# MCU.net
KiCad netlist of a schematic drawn in Altium Designer
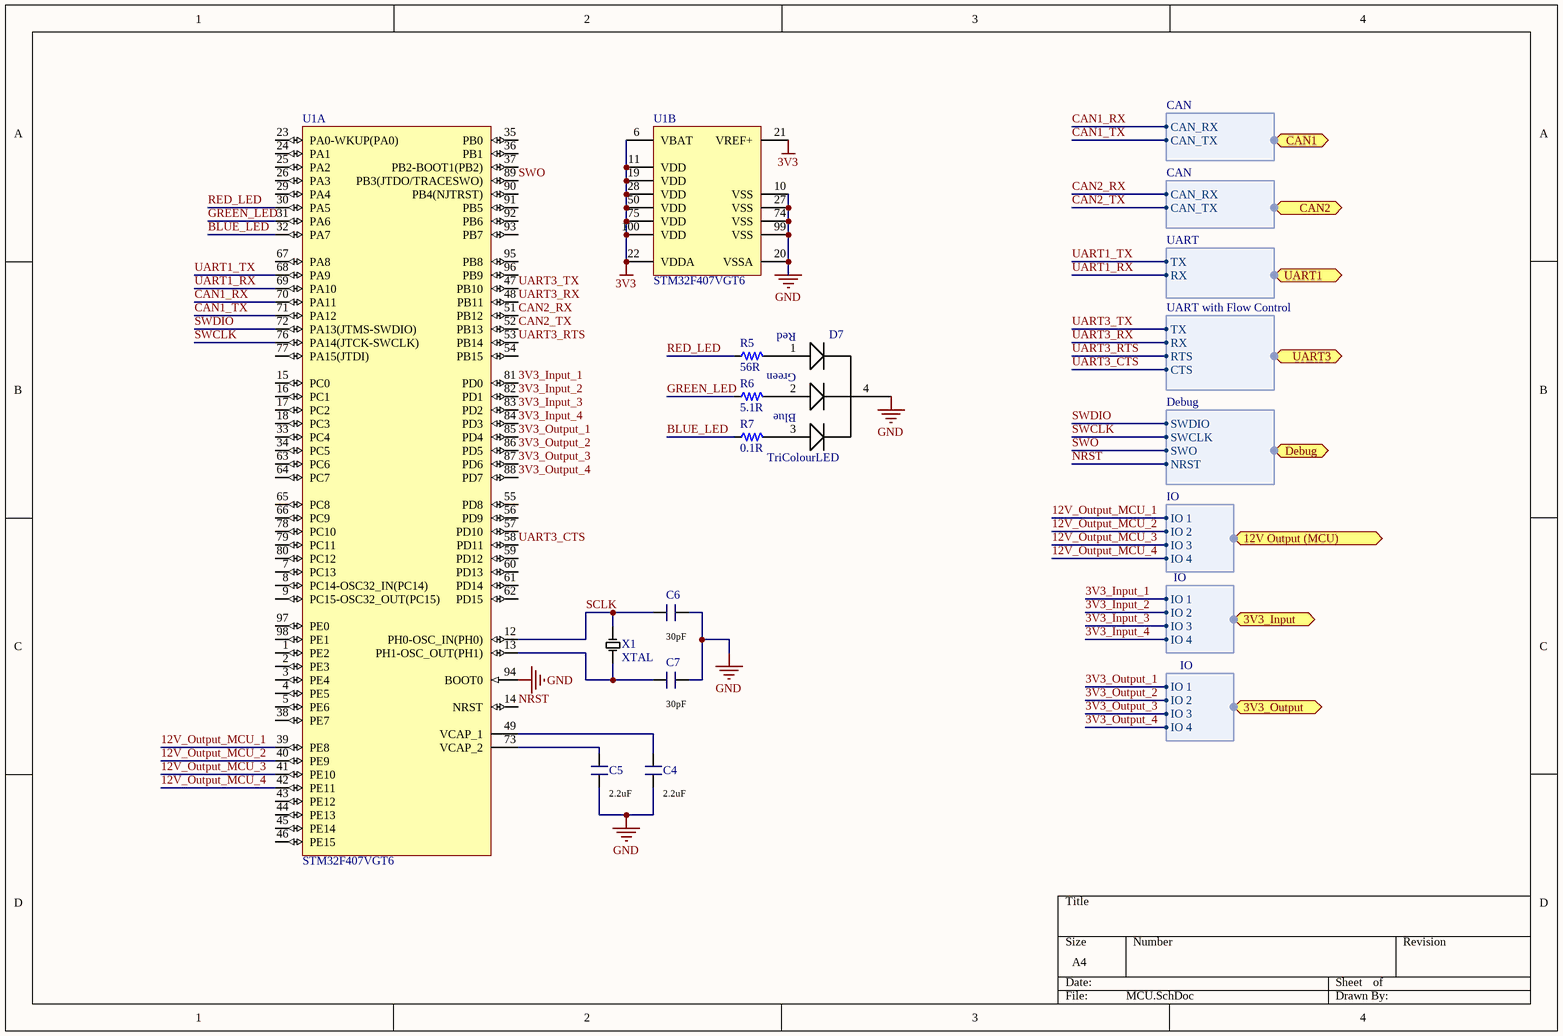
[diagram p0: MCU.SchDoc]

(export (version "E")
  (design (tool "Eeschema 10.0.6"))
  (components
    (comp (ref "C4")
      (value "SCH_GENERIC_CAPACITOR_0603")
      (footprint "PCB_GENERIC_SMD_0603")
      (description "Generic SMD capacitor 0603")
      (fields (field (name "TOLERANCE") "*%") (field (name "CAPACITANCE") "2.2uF"))
      (libsource (lib "Capacitors") (part "SCH_GENERIC_CAPACITOR_0603"))
    )
    (comp (ref "C5")
      (value "SCH_GENERIC_CAPACITOR_0603")
      (footprint "PCB_GENERIC_SMD_0603")
      (description "Generic SMD capacitor 0603")
      (fields (field (name "TOLERANCE") "*%") (field (name "CAPACITANCE") "2.2uF"))
      (libsource (lib "Capacitors") (part "SCH_GENERIC_CAPACITOR_0603"))
    )
    (comp (ref "C6")
      (value "SCH_GENERIC_CAPACITOR_0603")
      (footprint "PCB_GENERIC_SMD_0603")
      (description "Generic SMD capacitor 0603")
      (fields (field (name "TOLERANCE") "*%") (field (name "CAPACITANCE") "30pF"))
      (libsource (lib "Capacitors") (part "SCH_GENERIC_CAPACITOR_0603"))
    )
    (comp (ref "C7")
      (value "SCH_GENERIC_CAPACITOR_0603")
      (footprint "PCB_GENERIC_SMD_0603")
      (description "Generic SMD capacitor 0603")
      (fields (field (name "TOLERANCE") "*%") (field (name "CAPACITANCE") "30pF"))
      (libsource (lib "Capacitors") (part "SCH_GENERIC_CAPACITOR_0603"))
    )
    (comp (ref "D7")
      (value "TriColourLED")
      (footprint "TricolourLED - SunLED - DK  1497-1225-2-ND")
      (libsource (lib "TricolourLED - SunLED - DK 1497-1225-2-ND") (part "TriColourLED"))
    )
    (comp (ref "R5")
      (value "SCH_GENERIC_RESISTOR_0603")
      (footprint "PCB_GENERIC_SMD_0603")
      (description "Generic SMD resistor 0603")
      (fields (field (name "RESISTANCE") "56R"))
      (libsource (lib "SCH_GENERIC_RESISTOR_0603") (part "SCH_GENERIC_RESISTOR_0603"))
    )
    (comp (ref "R6")
      (value "SCH_GENERIC_RESISTOR_0603")
      (footprint "PCB_GENERIC_SMD_0603")
      (description "Generic SMD resistor 0603")
      (fields (field (name "RESISTANCE") "5.1R"))
      (libsource (lib "SCH_GENERIC_RESISTOR_0603") (part "SCH_GENERIC_RESISTOR_0603"))
    )
    (comp (ref "R7")
      (value "SCH_GENERIC_RESISTOR_0603")
      (footprint "PCB_GENERIC_SMD_0603")
      (description "Generic SMD resistor 0603")
      (fields (field (name "RESISTANCE") "0.1R"))
      (libsource (lib "SCH_GENERIC_RESISTOR_0603") (part "SCH_GENERIC_RESISTOR_0603"))
    )
    (comp (ref "U1")
      (value "STM32F407VGT6")
      (footprint "STM-LQFP100_M")
      (fields (field (name "MANUFACTURER") "STMicroelectronics"))
      (libsource (lib "STMicroelectronics STM32 F4") (part "STM32F407VGT6"))
    )
    (comp (ref "X1") (value "XTAL") (footprint "CRYSTAL_8MHZ") (libsource (lib "Crystal") (part "Crystal")))
  )
  (nets
    (net (code "8") (name "/3V3_Input_1") (class "Default")
      (node (ref "U1") (pin "81") (pinfunction "PD0_81") (pintype "bidirectional"))
    )
    (net (code "9") (name "/3V3_Input_2") (class "Default")
      (node (ref "U1") (pin "82") (pinfunction "PD1_82") (pintype "bidirectional"))
    )
    (net (code "10") (name "/3V3_Input_3") (class "Default")
      (node (ref "U1") (pin "83") (pinfunction "PD2_83") (pintype "bidirectional"))
    )
    (net (code "11") (name "/3V3_Input_4") (class "Default")
      (node (ref "U1") (pin "84") (pinfunction "PD3_84") (pintype "bidirectional"))
    )
    (net (code "12") (name "/3V3_Output_1") (class "Default")
      (node (ref "U1") (pin "85") (pinfunction "PD4_85") (pintype "bidirectional"))
    )
    (net (code "13") (name "/3V3_Output_2") (class "Default")
      (node (ref "U1") (pin "86") (pinfunction "PD5_86") (pintype "bidirectional"))
    )
    (net (code "14") (name "/3V3_Output_3") (class "Default")
      (node (ref "U1") (pin "87") (pinfunction "PD6_87") (pintype "bidirectional"))
    )
    (net (code "15") (name "/3V3_Output_4") (class "Default")
      (node (ref "U1") (pin "88") (pinfunction "PD7_88") (pintype "bidirectional"))
    )
    (net (code "16") (name "/12V_Output_MCU_1") (class "Default")
      (node (ref "U1") (pin "39") (pinfunction "PE8_39") (pintype "bidirectional"))
    )
    (net (code "17") (name "/12V_Output_MCU_2") (class "Default")
      (node (ref "U1") (pin "40") (pinfunction "PE9_40") (pintype "bidirectional"))
    )
    (net (code "18") (name "/12V_Output_MCU_3") (class "Default")
      (node (ref "U1") (pin "41") (pinfunction "PE10_41") (pintype "bidirectional"))
    )
    (net (code "19") (name "/12V_Output_MCU_4") (class "Default")
      (node (ref "U1") (pin "42") (pinfunction "PE11_42") (pintype "bidirectional"))
    )
    (net (code "20") (name "/BLUE_LED") (class "Default")
      (node (ref "R7") (pin "1") (pinfunction "1_1") (pintype "passive"))
      (node (ref "U1") (pin "32") (pinfunction "PA7_32") (pintype "bidirectional"))
    )
    (net (code "21") (name "/CAN1_RX") (class "Default")
      (node (ref "U1") (pin "70") (pinfunction "PA11_70") (pintype "bidirectional"))
    )
    (net (code "22") (name "/CAN1_TX") (class "Default")
      (node (ref "U1") (pin "71") (pinfunction "PA12_71") (pintype "bidirectional"))
    )
    (net (code "23") (name "/CAN2_RX") (class "Default")
      (node (ref "U1") (pin "51") (pinfunction "PB12_51") (pintype "bidirectional"))
    )
    (net (code "24") (name "/CAN2_TX") (class "Default")
      (node (ref "U1") (pin "52") (pinfunction "PB13_52") (pintype "bidirectional"))
    )
    (net (code "25") (name "/GREEN_LED") (class "Default")
      (node (ref "R6") (pin "1") (pinfunction "1_1") (pintype "passive"))
      (node (ref "U1") (pin "31") (pinfunction "PA6_31") (pintype "bidirectional"))
    )
    (net (code "26") (name "/NRST") (class "Default")
      (node (ref "U1") (pin "14") (pinfunction "NRST_14") (pintype "bidirectional"))
    )
    (net (code "27") (name "/RED_LED") (class "Default")
      (node (ref "R5") (pin "1") (pinfunction "1_1") (pintype "passive"))
      (node (ref "U1") (pin "30") (pinfunction "PA5_30") (pintype "bidirectional"))
    )
    (net (code "28") (name "/SCLK") (class "Default")
      (node (ref "C6") (pin "2") (pinfunction "2_2") (pintype "passive"))
      (node (ref "U1") (pin "12") (pinfunction "PH0-OSC_IN(PH0)_12") (pintype "bidirectional"))
      (node (ref "X1") (pin "1") (pintype "passive"))
    )
    (net (code "29") (name "/SWCLK") (class "Default")
      (node (ref "U1") (pin "76") (pinfunction "PA14(JTCK-SWCLK)_76") (pintype "bidirectional"))
    )
    (net (code "30") (name "/SWDIO") (class "Default")
      (node (ref "U1") (pin "72") (pinfunction "PA13(JTMS-SWDIO)_72") (pintype "bidirectional"))
    )
    (net (code "31") (name "/SWO") (class "Default")
      (node (ref "U1") (pin "89") (pinfunction "PB3(JTDO/TRACESWO)_89") (pintype "bidirectional"))
    )
    (net (code "32") (name "/UART1_RX") (class "Default")
      (node (ref "U1") (pin "69") (pinfunction "PA10_69") (pintype "bidirectional"))
    )
    (net (code "33") (name "/UART1_TX") (class "Default")
      (node (ref "U1") (pin "68") (pinfunction "PA9_68") (pintype "bidirectional"))
    )
    (net (code "34") (name "/UART3_CTS") (class "Default")
      (node (ref "U1") (pin "58") (pinfunction "PD11_58") (pintype "bidirectional"))
    )
    (net (code "35") (name "/UART3_RTS") (class "Default")
      (node (ref "U1") (pin "53") (pinfunction "PB14_53") (pintype "bidirectional"))
    )
    (net (code "36") (name "/UART3_RX") (class "Default")
      (node (ref "U1") (pin "48") (pinfunction "PB11_48") (pintype "bidirectional"))
    )
    (net (code "37") (name "/UART3_TX") (class "Default")
      (node (ref "U1") (pin "47") (pinfunction "PB10_47") (pintype "bidirectional"))
    )
    (net (code "43") (name "3V3") (class "Default")
      (node (ref "U1") (pin "100") (pinfunction "VDD_100") (pintype "power_in"))
      (node (ref "U1") (pin "11") (pinfunction "VDD_11") (pintype "power_in"))
      (node (ref "U1") (pin "19") (pinfunction "VDD_19") (pintype "power_in"))
      (node (ref "U1") (pin "21") (pinfunction "VREF+_21") (pintype "power_in"))
      (node (ref "U1") (pin "22") (pinfunction "VDDA_22") (pintype "power_in"))
      (node (ref "U1") (pin "28") (pinfunction "VDD_28") (pintype "power_in"))
      (node (ref "U1") (pin "50") (pinfunction "VDD_50") (pintype "power_in"))
      (node (ref "U1") (pin "6") (pinfunction "VBAT_6") (pintype "power_in"))
      (node (ref "U1") (pin "75") (pinfunction "VDD_75") (pintype "power_in"))
    )
    (net (code "44") (name "GND") (class "Default")
      (node (ref "C4") (pin "1") (pinfunction "1_1") (pintype "passive"))
      (node (ref "C5") (pin "1") (pinfunction "1_1") (pintype "passive"))
      (node (ref "C6") (pin "1") (pinfunction "1_1") (pintype "passive"))
      (node (ref "C7") (pin "1") (pinfunction "1_1") (pintype "passive"))
      (node (ref "D7") (pin "4") (pinfunction "4_4") (pintype "passive"))
      (node (ref "U1") (pin "10") (pinfunction "VSS_10") (pintype "power_in"))
      (node (ref "U1") (pin "20") (pinfunction "VSSA_20") (pintype "power_in"))
      (node (ref "U1") (pin "27") (pinfunction "VSS_27") (pintype "power_in"))
      (node (ref "U1") (pin "74") (pinfunction "VSS_74") (pintype "power_in"))
      (node (ref "U1") (pin "94") (pinfunction "BOOT0_94") (pintype "input"))
      (node (ref "U1") (pin "99") (pinfunction "VSS_99") (pintype "power_in"))
    )
    (net (code "45") (name "Net-(D7-Blue)") (class "Default")
      (node (ref "D7") (pin "3") (pinfunction "Blue_3") (pintype "passive"))
      (node (ref "R7") (pin "2") (pinfunction "2_2") (pintype "passive"))
    )
    (net (code "46") (name "Net-(D7-Green)") (class "Default")
      (node (ref "D7") (pin "2") (pinfunction "Green_2") (pintype "passive"))
      (node (ref "R6") (pin "2") (pinfunction "2_2") (pintype "passive"))
    )
    (net (code "47") (name "Net-(D7-Red)") (class "Default")
      (node (ref "D7") (pin "1") (pinfunction "Red_1") (pintype "passive"))
      (node (ref "R5") (pin "2") (pinfunction "2_2") (pintype "passive"))
    )
    (net (code "48") (name "Net-(U1A-PH1-OSC_OUT(PH1))") (class "Default")
      (node (ref "C7") (pin "2") (pinfunction "2_2") (pintype "passive"))
      (node (ref "U1") (pin "13") (pinfunction "PH1-OSC_OUT(PH1)_13") (pintype "bidirectional"))
      (node (ref "X1") (pin "2") (pintype "passive"))
    )
    (net (code "49") (name "Net-(U1A-VCAP_1)") (class "Default")
      (node (ref "C4") (pin "2") (pinfunction "2_2") (pintype "passive"))
      (node (ref "U1") (pin "49") (pinfunction "VCAP_1_49") (pintype "power_in"))
    )
    (net (code "50") (name "Net-(U1A-VCAP_2)") (class "Default")
      (node (ref "C5") (pin "2") (pinfunction "2_2") (pintype "passive"))
      (node (ref "U1") (pin "73") (pinfunction "VCAP_2_73") (pintype "power_in"))
    )
    (net (code "51") (name "unconnected-(U1A-PA0-WKUP(PA0)-Pad23)") (class "Default")
      (node (ref "U1") (pin "23") (pinfunction "PA0-WKUP(PA0)_23") (pintype "bidirectional"))
    )
    (net (code "52") (name "unconnected-(U1A-PA1-Pad24)") (class "Default")
      (node (ref "U1") (pin "24") (pinfunction "PA1_24") (pintype "bidirectional"))
    )
    (net (code "53") (name "unconnected-(U1A-PA2-Pad25)") (class "Default")
      (node (ref "U1") (pin "25") (pinfunction "PA2_25") (pintype "bidirectional"))
    )
    (net (code "54") (name "unconnected-(U1A-PA3-Pad26)") (class "Default")
      (node (ref "U1") (pin "26") (pinfunction "PA3_26") (pintype "bidirectional"))
    )
    (net (code "55") (name "unconnected-(U1A-PA4-Pad29)") (class "Default")
      (node (ref "U1") (pin "29") (pinfunction "PA4_29") (pintype "bidirectional"))
    )
    (net (code "56") (name "unconnected-(U1A-PA8-Pad67)") (class "Default")
      (node (ref "U1") (pin "67") (pinfunction "PA8_67") (pintype "bidirectional"))
    )
    (net (code "57") (name "unconnected-(U1A-PA15(JTDI)-Pad77)") (class "Default")
      (node (ref "U1") (pin "77") (pinfunction "PA15(JTDI)_77") (pintype "bidirectional"))
    )
    (net (code "58") (name "unconnected-(U1A-PB0-Pad35)") (class "Default")
      (node (ref "U1") (pin "35") (pinfunction "PB0_35") (pintype "bidirectional"))
    )
    (net (code "59") (name "unconnected-(U1A-PB1-Pad36)") (class "Default")
      (node (ref "U1") (pin "36") (pinfunction "PB1_36") (pintype "bidirectional"))
    )
    (net (code "60") (name "unconnected-(U1A-PB2-BOOT1(PB2)-Pad37)") (class "Default")
      (node (ref "U1") (pin "37") (pinfunction "PB2-BOOT1(PB2)_37") (pintype "bidirectional"))
    )
    (net (code "61") (name "unconnected-(U1A-PB4(NJTRST)-Pad90)") (class "Default")
      (node (ref "U1") (pin "90") (pinfunction "PB4(NJTRST)_90") (pintype "bidirectional"))
    )
    (net (code "62") (name "unconnected-(U1A-PB5-Pad91)") (class "Default")
      (node (ref "U1") (pin "91") (pinfunction "PB5_91") (pintype "bidirectional"))
    )
    (net (code "63") (name "unconnected-(U1A-PB6-Pad92)") (class "Default")
      (node (ref "U1") (pin "92") (pinfunction "PB6_92") (pintype "bidirectional"))
    )
    (net (code "64") (name "unconnected-(U1A-PB7-Pad93)") (class "Default")
      (node (ref "U1") (pin "93") (pinfunction "PB7_93") (pintype "bidirectional"))
    )
    (net (code "65") (name "unconnected-(U1A-PB8-Pad95)") (class "Default")
      (node (ref "U1") (pin "95") (pinfunction "PB8_95") (pintype "bidirectional"))
    )
    (net (code "66") (name "unconnected-(U1A-PB9-Pad96)") (class "Default")
      (node (ref "U1") (pin "96") (pinfunction "PB9_96") (pintype "bidirectional"))
    )
    (net (code "67") (name "unconnected-(U1A-PB15-Pad54)") (class "Default")
      (node (ref "U1") (pin "54") (pinfunction "PB15_54") (pintype "bidirectional"))
    )
    (net (code "68") (name "unconnected-(U1A-PC0-Pad15)") (class "Default")
      (node (ref "U1") (pin "15") (pinfunction "PC0_15") (pintype "bidirectional"))
    )
    (net (code "69") (name "unconnected-(U1A-PC1-Pad16)") (class "Default")
      (node (ref "U1") (pin "16") (pinfunction "PC1_16") (pintype "bidirectional"))
    )
    (net (code "70") (name "unconnected-(U1A-PC2-Pad17)") (class "Default")
      (node (ref "U1") (pin "17") (pinfunction "PC2_17") (pintype "bidirectional"))
    )
    (net (code "71") (name "unconnected-(U1A-PC3-Pad18)") (class "Default")
      (node (ref "U1") (pin "18") (pinfunction "PC3_18") (pintype "bidirectional"))
    )
    (net (code "72") (name "unconnected-(U1A-PC4-Pad33)") (class "Default")
      (node (ref "U1") (pin "33") (pinfunction "PC4_33") (pintype "bidirectional"))
    )
    (net (code "73") (name "unconnected-(U1A-PC5-Pad34)") (class "Default")
      (node (ref "U1") (pin "34") (pinfunction "PC5_34") (pintype "bidirectional"))
    )
    (net (code "74") (name "unconnected-(U1A-PC6-Pad63)") (class "Default")
      (node (ref "U1") (pin "63") (pinfunction "PC6_63") (pintype "bidirectional"))
    )
    (net (code "75") (name "unconnected-(U1A-PC7-Pad64)") (class "Default")
      (node (ref "U1") (pin "64") (pinfunction "PC7_64") (pintype "bidirectional"))
    )
    (net (code "76") (name "unconnected-(U1A-PC8-Pad65)") (class "Default")
      (node (ref "U1") (pin "65") (pinfunction "PC8_65") (pintype "bidirectional"))
    )
    (net (code "77") (name "unconnected-(U1A-PC9-Pad66)") (class "Default")
      (node (ref "U1") (pin "66") (pinfunction "PC9_66") (pintype "bidirectional"))
    )
    (net (code "78") (name "unconnected-(U1A-PC10-Pad78)") (class "Default")
      (node (ref "U1") (pin "78") (pinfunction "PC10_78") (pintype "bidirectional"))
    )
    (net (code "79") (name "unconnected-(U1A-PC11-Pad79)") (class "Default")
      (node (ref "U1") (pin "79") (pinfunction "PC11_79") (pintype "bidirectional"))
    )
    (net (code "80") (name "unconnected-(U1A-PC12-Pad80)") (class "Default")
      (node (ref "U1") (pin "80") (pinfunction "PC12_80") (pintype "bidirectional"))
    )
    (net (code "81") (name "unconnected-(U1A-PC13-Pad7)") (class "Default")
      (node (ref "U1") (pin "7") (pinfunction "PC13_7") (pintype "bidirectional"))
    )
    (net (code "82") (name "unconnected-(U1A-PC14-OSC32_IN(PC14)-Pad8)") (class "Default")
      (node (ref "U1") (pin "8") (pinfunction "PC14-OSC32_IN(PC14)_8") (pintype "bidirectional"))
    )
    (net (code "83") (name "unconnected-(U1A-PC15-OSC32_OUT(PC15)-Pad9)") (class "Default")
      (node (ref "U1") (pin "9") (pinfunction "PC15-OSC32_OUT(PC15)_9") (pintype "bidirectional"))
    )
    (net (code "84") (name "unconnected-(U1A-PD8-Pad55)") (class "Default")
      (node (ref "U1") (pin "55") (pinfunction "PD8_55") (pintype "bidirectional"))
    )
    (net (code "85") (name "unconnected-(U1A-PD9-Pad56)") (class "Default")
      (node (ref "U1") (pin "56") (pinfunction "PD9_56") (pintype "bidirectional"))
    )
    (net (code "86") (name "unconnected-(U1A-PD10-Pad57)") (class "Default")
      (node (ref "U1") (pin "57") (pinfunction "PD10_57") (pintype "bidirectional"))
    )
    (net (code "87") (name "unconnected-(U1A-PD12-Pad59)") (class "Default")
      (node (ref "U1") (pin "59") (pinfunction "PD12_59") (pintype "bidirectional"))
    )
    (net (code "88") (name "unconnected-(U1A-PD13-Pad60)") (class "Default")
      (node (ref "U1") (pin "60") (pinfunction "PD13_60") (pintype "bidirectional"))
    )
    (net (code "89") (name "unconnected-(U1A-PD14-Pad61)") (class "Default")
      (node (ref "U1") (pin "61") (pinfunction "PD14_61") (pintype "bidirectional"))
    )
    (net (code "90") (name "unconnected-(U1A-PD15-Pad62)") (class "Default")
      (node (ref "U1") (pin "62") (pinfunction "PD15_62") (pintype "bidirectional"))
    )
    (net (code "91") (name "unconnected-(U1A-PE0-Pad97)") (class "Default")
      (node (ref "U1") (pin "97") (pinfunction "PE0_97") (pintype "bidirectional"))
    )
    (net (code "92") (name "unconnected-(U1A-PE1-Pad98)") (class "Default")
      (node (ref "U1") (pin "98") (pinfunction "PE1_98") (pintype "bidirectional"))
    )
    (net (code "93") (name "unconnected-(U1A-PE2-Pad1)") (class "Default")
      (node (ref "U1") (pin "1") (pinfunction "PE2_1") (pintype "bidirectional"))
    )
    (net (code "94") (name "unconnected-(U1A-PE3-Pad2)") (class "Default")
      (node (ref "U1") (pin "2") (pinfunction "PE3_2") (pintype "bidirectional"))
    )
    (net (code "95") (name "unconnected-(U1A-PE4-Pad3)") (class "Default")
      (node (ref "U1") (pin "3") (pinfunction "PE4_3") (pintype "bidirectional"))
    )
    (net (code "96") (name "unconnected-(U1A-PE5-Pad4)") (class "Default")
      (node (ref "U1") (pin "4") (pinfunction "PE5_4") (pintype "bidirectional"))
    )
    (net (code "97") (name "unconnected-(U1A-PE6-Pad5)") (class "Default")
      (node (ref "U1") (pin "5") (pinfunction "PE6_5") (pintype "bidirectional"))
    )
    (net (code "98") (name "unconnected-(U1A-PE7-Pad38)") (class "Default")
      (node (ref "U1") (pin "38") (pinfunction "PE7_38") (pintype "bidirectional"))
    )
    (net (code "99") (name "unconnected-(U1A-PE12-Pad43)") (class "Default")
      (node (ref "U1") (pin "43") (pinfunction "PE12_43") (pintype "bidirectional"))
    )
    (net (code "100") (name "unconnected-(U1A-PE13-Pad44)") (class "Default")
      (node (ref "U1") (pin "44") (pinfunction "PE13_44") (pintype "bidirectional"))
    )
    (net (code "101") (name "unconnected-(U1A-PE14-Pad45)") (class "Default")
      (node (ref "U1") (pin "45") (pinfunction "PE14_45") (pintype "bidirectional"))
    )
    (net (code "102") (name "unconnected-(U1A-PE15-Pad46)") (class "Default")
      (node (ref "U1") (pin "46") (pinfunction "PE15_46") (pintype "bidirectional"))
    )
  )
)
